# dclass-amp.net
KiCad netlist of a schematic drawn in Altium Designer
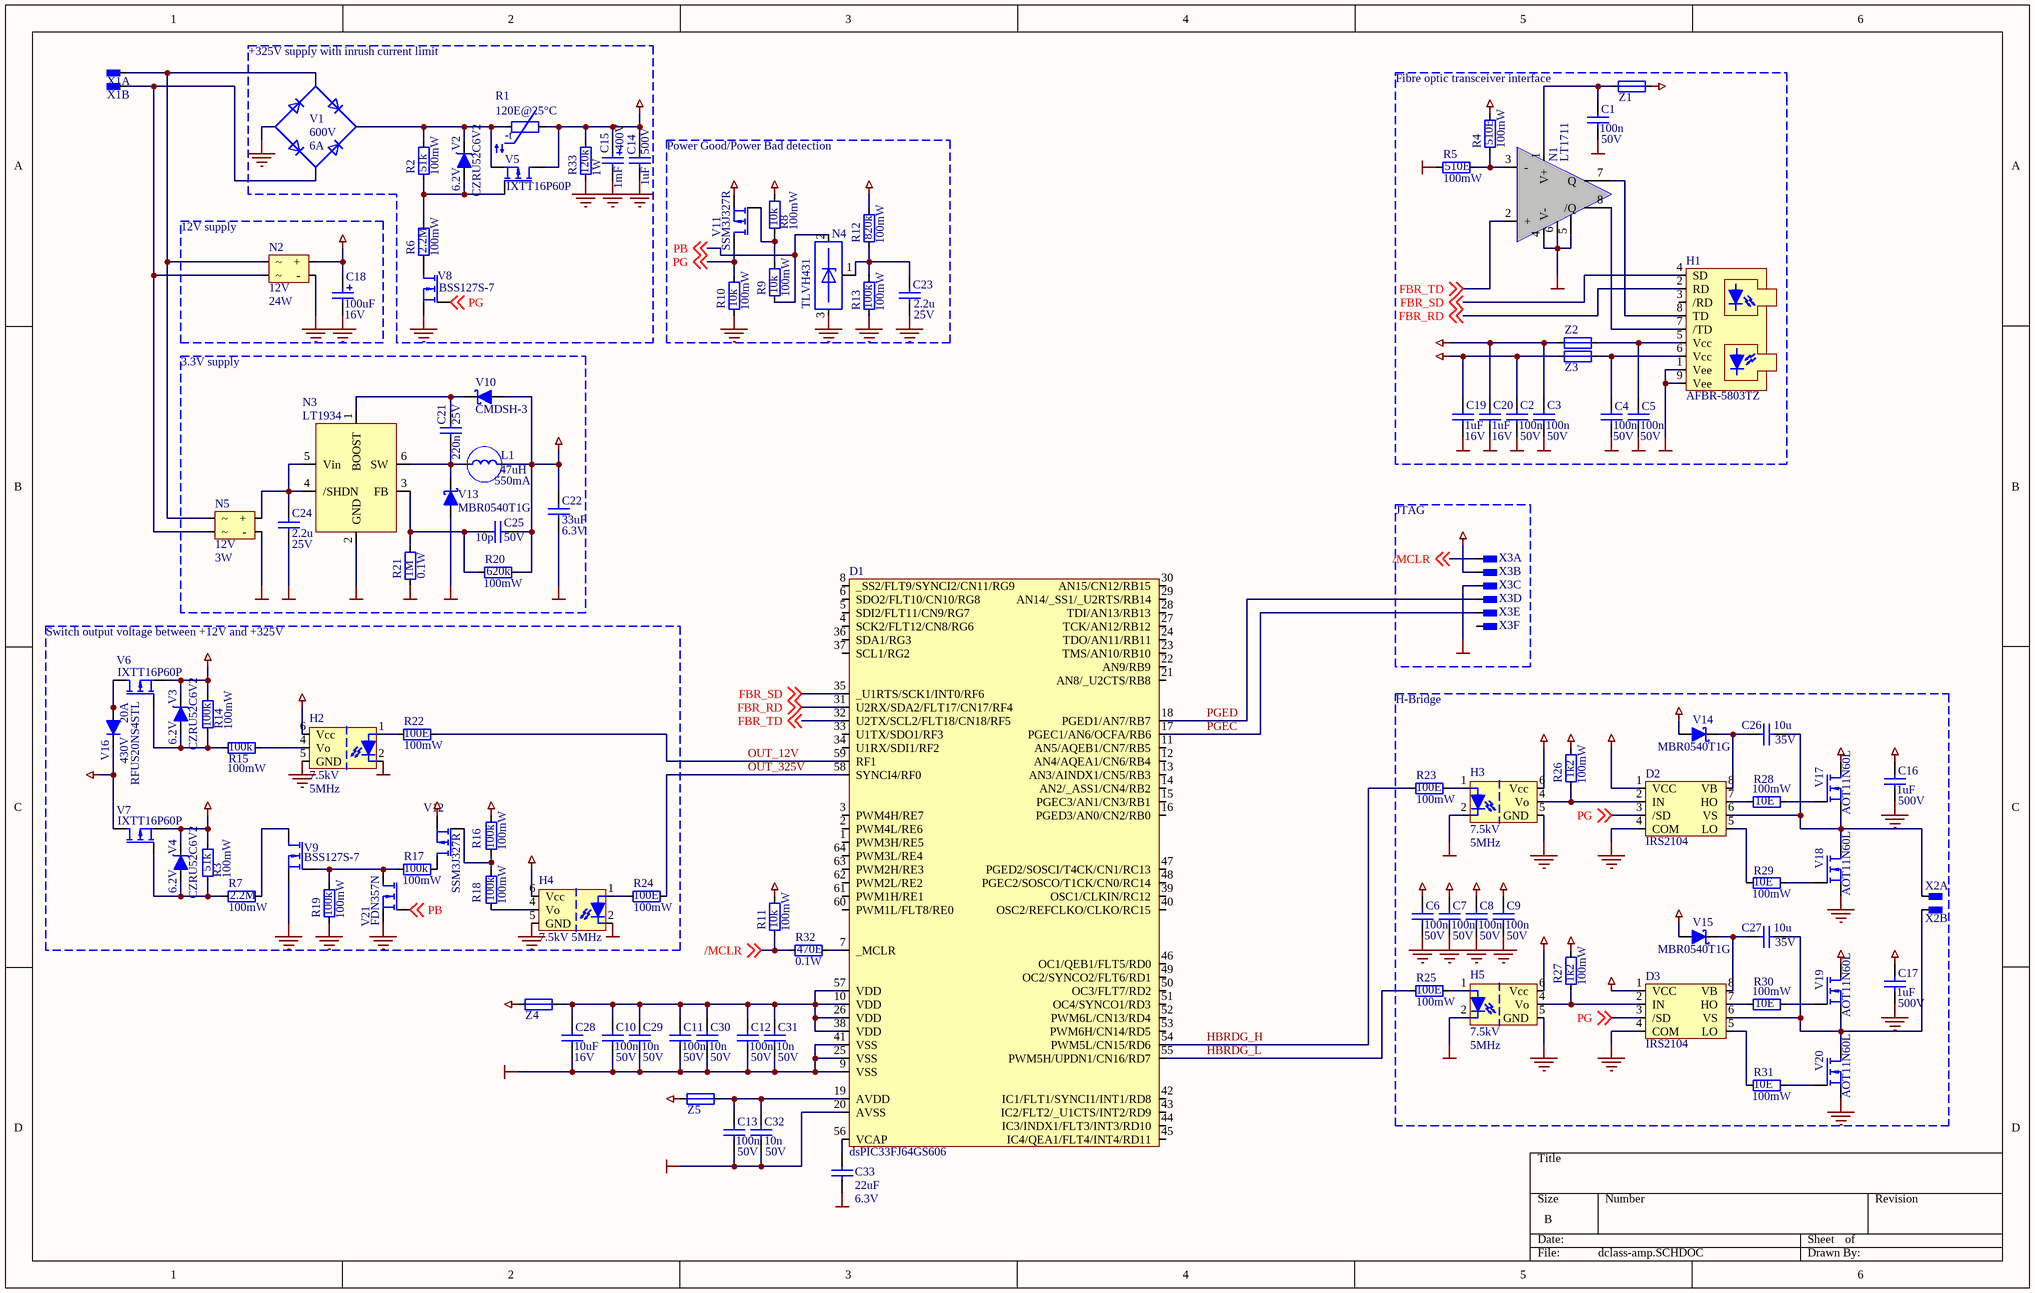
[diagram p0: dclass-amp.SCHDOC]

(export (version "E")
  (design (tool "Eeschema 10.0.6"))
  (components
    (comp (ref "C1")
      (value "C_SMD_CER_100N_50V_10%_X7R_0603")
      (footprint "SMD_0603")
      (description "SMD Capacitor")
      (fields (field (name "ALTIUM_VALUE") "100n") (field (name "VALUE2") "50V"))
      (libsource (lib "AM") (part "C_SMD_CER_100N_50V_10%_X7R_0603"))
    )
    (comp (ref "C2")
      (value "C_SMD_CER_100N_50V_10%_X7R_0603")
      (footprint "SMD_0603")
      (description "SMD Capacitor")
      (fields (field (name "ALTIUM_VALUE") "100n") (field (name "VALUE2") "50V"))
      (libsource (lib "AM") (part "C_SMD_CER_100N_50V_10%_X7R_0603"))
    )
    (comp (ref "C3")
      (value "C_SMD_CER_100N_50V_10%_X7R_0603")
      (footprint "SMD_0603")
      (description "SMD Capacitor")
      (fields (field (name "ALTIUM_VALUE") "100n") (field (name "VALUE2") "50V"))
      (libsource (lib "AM") (part "C_SMD_CER_100N_50V_10%_X7R_0603"))
    )
    (comp (ref "C4")
      (value "C_SMD_CER_100N_50V_10%_X7R_0603")
      (footprint "SMD_0603")
      (description "SMD Capacitor")
      (fields (field (name "ALTIUM_VALUE") "100n") (field (name "VALUE2") "50V"))
      (libsource (lib "AM") (part "C_SMD_CER_100N_50V_10%_X7R_0603"))
    )
    (comp (ref "C5")
      (value "C_SMD_CER_100N_50V_10%_X7R_0603")
      (footprint "SMD_0603")
      (description "SMD Capacitor")
      (fields (field (name "ALTIUM_VALUE") "100n") (field (name "VALUE2") "50V"))
      (libsource (lib "AM") (part "C_SMD_CER_100N_50V_10%_X7R_0603"))
    )
    (comp (ref "C6")
      (value "C_SMD_CER_100N_50V_10%_X7R_0603")
      (footprint "SMD_0603")
      (description "SMD Capacitor")
      (fields (field (name "ALTIUM_VALUE") "100n") (field (name "VALUE2") "50V"))
      (libsource (lib "AM") (part "C_SMD_CER_100N_50V_10%_X7R_0603"))
    )
    (comp (ref "C7")
      (value "C_SMD_CER_100N_50V_10%_X7R_0603")
      (footprint "SMD_0603")
      (description "SMD Capacitor")
      (fields (field (name "ALTIUM_VALUE") "100n") (field (name "VALUE2") "50V"))
      (libsource (lib "AM") (part "C_SMD_CER_100N_50V_10%_X7R_0603"))
    )
    (comp (ref "C8")
      (value "C_SMD_CER_100N_50V_10%_X7R_0603")
      (footprint "SMD_0603")
      (description "SMD Capacitor")
      (fields (field (name "ALTIUM_VALUE") "100n") (field (name "VALUE2") "50V"))
      (libsource (lib "AM") (part "C_SMD_CER_100N_50V_10%_X7R_0603"))
    )
    (comp (ref "C9")
      (value "C_SMD_CER_100N_50V_10%_X7R_0603")
      (footprint "SMD_0603")
      (description "SMD Capacitor")
      (fields (field (name "ALTIUM_VALUE") "100n") (field (name "VALUE2") "50V"))
      (libsource (lib "AM") (part "C_SMD_CER_100N_50V_10%_X7R_0603"))
    )
    (comp (ref "C10")
      (value "C_SMD_CER_100N_50V_10%_X7R_0603")
      (footprint "SMD_0603")
      (description "SMD Capacitor")
      (fields (field (name "ALTIUM_VALUE") "100n") (field (name "VALUE2") "50V"))
      (libsource (lib "AM") (part "C_SMD_CER_100N_50V_10%_X7R_0603"))
    )
    (comp (ref "C11")
      (value "C_SMD_CER_100N_50V_10%_X7R_0603")
      (footprint "SMD_0603")
      (description "SMD Capacitor")
      (fields (field (name "ALTIUM_VALUE") "100n") (field (name "VALUE2") "50V"))
      (libsource (lib "AM") (part "C_SMD_CER_100N_50V_10%_X7R_0603"))
    )
    (comp (ref "C12")
      (value "C_SMD_CER_100N_50V_10%_X7R_0603")
      (footprint "SMD_0603")
      (description "SMD Capacitor")
      (fields (field (name "ALTIUM_VALUE") "100n") (field (name "VALUE2") "50V"))
      (libsource (lib "AM") (part "C_SMD_CER_100N_50V_10%_X7R_0603"))
    )
    (comp (ref "C13")
      (value "C_SMD_CER_100N_50V_10%_X7R_0603")
      (footprint "SMD_0603")
      (description "SMD Capacitor")
      (fields (field (name "ALTIUM_VALUE") "100n") (field (name "VALUE2") "50V"))
      (libsource (lib "AM") (part "C_SMD_CER_100N_50V_10%_X7R_0603"))
    )
    (comp (ref "C14")
      (value "C_THT_ALU_1000U_400V_20%_T2GP102FA")
      (footprint "THT_CAP_T2GP102FA")
      (description "THT Aluminum capacitor")
      (fields (field (name "ALTIUM_VALUE") "1mF") (field (name "VALUE2") "400V"))
      (libsource (lib "AM") (part "C_THT_ALU_1000U_400V_20%_T2GP102FA"))
    )
    (comp (ref "C15")
      (value "C_SMD_CER_1U_500V_20%_X7R_2220")
      (footprint "SMD_2220")
      (fields (field (name "ALTIUM_VALUE") "1uF") (field (name "VALUE2") "500V"))
      (libsource (lib "AM") (part "C_SMD_CER_1U_500V_20%_X7R_2220"))
    )
    (comp (ref "C16")
      (value "C_SMD_CER_1U_500V_20%_X7R_2220")
      (footprint "SMD_2220")
      (fields (field (name "ALTIUM_VALUE") "1uF") (field (name "VALUE2") "500V"))
      (libsource (lib "AM") (part "C_SMD_CER_1U_500V_20%_X7R_2220"))
    )
    (comp (ref "C17")
      (value "C_SMD_CER_1U_500V_20%_X7R_2220")
      (footprint "SMD_2220")
      (fields (field (name "ALTIUM_VALUE") "1uF") (field (name "VALUE2") "500V"))
      (libsource (lib "AM") (part "C_SMD_CER_1U_500V_20%_X7R_2220"))
    )
    (comp (ref "C18")
      (value "C_SMD_TAN_100U_16V_20%_7343")
      (footprint "SMD_7343P")
      (description "SMD Tantal Capacitor")
      (fields (field (name "ALTIUM_VALUE") "100uF") (field (name "VALUE2") "16V"))
      (libsource (lib "AM") (part "C_SMD_TAN_100U_16V_20%_7343"))
    )
    (comp (ref "C19")
      (value "C_SMD_CER_1U_16V_10%_X5R_0603")
      (footprint "SMD_0603")
      (description "SMD Capacitor")
      (fields (field (name "ALTIUM_VALUE") "1uF") (field (name "VALUE2") "16V"))
      (libsource (lib "AM") (part "C_SMD_CER_1U_16V_10%_X5R_0603"))
    )
    (comp (ref "C20")
      (value "C_SMD_CER_1U_16V_10%_X5R_0603")
      (footprint "SMD_0603")
      (description "SMD Capacitor")
      (fields (field (name "ALTIUM_VALUE") "1uF") (field (name "VALUE2") "16V"))
      (libsource (lib "AM") (part "C_SMD_CER_1U_16V_10%_X5R_0603"))
    )
    (comp (ref "C21")
      (value "C_SMD_CER_220N_25V_10%_X5R_0603")
      (footprint "SMD_0603")
      (description "SMD Capacitor")
      (fields (field (name "ALTIUM_VALUE") "220n") (field (name "VALUE2") "25V"))
      (libsource (lib "AM") (part "C_SMD_CER_220N_25V_10%_X5R_0603"))
    )
    (comp (ref "C22")
      (value "C_SMD_CER_33U_6V3_20%_X5R_1206")
      (footprint "SMD_1206")
      (fields (field (name "ALTIUM_VALUE") "33uF") (field (name "VALUE2") "6.3V"))
      (libsource (lib "AM") (part "C_SMD_CER_33U_6V3_20%_X5R_1206"))
    )
    (comp (ref "C23")
      (value "C_SMD_CER_2U2_25V_10%_X5R_0603")
      (footprint "SMD_0603")
      (description "SMD Capacitor")
      (fields (field (name "ALTIUM_VALUE") "2.2u") (field (name "VALUE2") "25V"))
      (libsource (lib "AM") (part "C_SMD_CER_2U2_25V_10%_X5R_0603"))
    )
    (comp (ref "C24")
      (value "C_SMD_CER_2U2_25V_10%_X5R_0603")
      (footprint "SMD_0603")
      (description "SMD Capacitor")
      (fields (field (name "ALTIUM_VALUE") "2.2u") (field (name "VALUE2") "25V"))
      (libsource (lib "AM") (part "C_SMD_CER_2U2_25V_10%_X5R_0603"))
    )
    (comp (ref "C25")
      (value "C_SMD_CER_10P_50V_5%_NP0_0603")
      (footprint "SMD_0603")
      (description "SMD Capacitor")
      (fields (field (name "ALTIUM_VALUE") "10p") (field (name "VALUE2") "50V"))
      (libsource (lib "AM") (part "C_SMD_CER_10P_50V_5%_NP0_0603"))
    )
    (comp (ref "C26")
      (value "C_SMD_CER_10U_35V_10%_X5R_1206")
      (footprint "SMD_1206")
      (description "SMD Capacitor, 10uF, 35V, 1206")
      (fields (field (name "ALTIUM_VALUE") "10u") (field (name "VALUE2") "35V"))
      (libsource (lib "AM") (part "C_SMD_CER_10U_35V_10%_X5R_1206"))
    )
    (comp (ref "C27")
      (value "C_SMD_CER_10U_35V_10%_X5R_1206")
      (footprint "SMD_1206")
      (description "SMD Capacitor, 10uF, 35V, 1206")
      (fields (field (name "ALTIUM_VALUE") "10u") (field (name "VALUE2") "35V"))
      (libsource (lib "AM") (part "C_SMD_CER_10U_35V_10%_X5R_1206"))
    )
    (comp (ref "C28")
      (value "C_SMD_CER_10U_16V_10%_X5R_0805")
      (footprint "SMD_0805")
      (description "SMD Capacitor")
      (fields (field (name "ALTIUM_VALUE") "10uF") (field (name "VALUE2") "16V"))
      (libsource (lib "AM") (part "C_SMD_CER_10U_16V_10%_X5R_0805"))
    )
    (comp (ref "C29")
      (value "C_SMD_CER_10N_50V_10%_X7R_0603")
      (footprint "SMD_0603")
      (description "SMD Capacitor")
      (fields (field (name "ALTIUM_VALUE") "10n") (field (name "VALUE2") "50V"))
      (libsource (lib "AM") (part "C_SMD_CER_10N_50V_10%_X7R_0603"))
    )
    (comp (ref "C30")
      (value "C_SMD_CER_10N_50V_10%_X7R_0603")
      (footprint "SMD_0603")
      (description "SMD Capacitor")
      (fields (field (name "ALTIUM_VALUE") "10n") (field (name "VALUE2") "50V"))
      (libsource (lib "AM") (part "C_SMD_CER_10N_50V_10%_X7R_0603"))
    )
    (comp (ref "C31")
      (value "C_SMD_CER_10N_50V_10%_X7R_0603")
      (footprint "SMD_0603")
      (description "SMD Capacitor")
      (fields (field (name "ALTIUM_VALUE") "10n") (field (name "VALUE2") "50V"))
      (libsource (lib "AM") (part "C_SMD_CER_10N_50V_10%_X7R_0603"))
    )
    (comp (ref "C32")
      (value "C_SMD_CER_10N_50V_10%_X7R_0603")
      (footprint "SMD_0603")
      (description "SMD Capacitor")
      (fields (field (name "ALTIUM_VALUE") "10n") (field (name "VALUE2") "50V"))
      (libsource (lib "AM") (part "C_SMD_CER_10N_50V_10%_X7R_0603"))
    )
    (comp (ref "C33")
      (value "C_SMD_CER_22U_6V3_20%_X5R_1206")
      (footprint "SMD_1206")
      (description "SMD Capacitor")
      (fields (field (name "ALTIUM_VALUE") "22uF") (field (name "VALUE2") "6.3V"))
      (libsource (lib "AM") (part "C_SMD_CER_22U_6V3_20%_X5R_1206"))
    )
    (comp (ref "D1")
      (value "D_DSPIC33FJ64GS606_TQFP-64")
      (footprint "SMD_TQFP-64")
      (fields (field (name "TYPE") "dsPIC33FJ64GS606"))
      (libsource (lib "AM") (part "D_DSPIC33FJ64GS606_TQFP-64"))
    )
    (comp (ref "D2")
      (value "D_IRS2104SPBF_SOP-8")
      (footprint "SMD_SOP_8")
      (description "Half-Bridge Driver, 600V")
      (fields (field (name "TYPE") "IRS2104"))
      (libsource (lib "AM") (part "D_IRS2104SPBF_SOP-8"))
    )
    (comp (ref "D3")
      (value "D_IRS2104SPBF_SOP-8")
      (footprint "SMD_SOP_8")
      (description "Half-Bridge Driver, 600V")
      (fields (field (name "TYPE") "IRS2104"))
      (libsource (lib "AM") (part "D_IRS2104SPBF_SOP-8"))
    )
    (comp (ref "H1")
      (value "H_OPTO_TRANSCEIVER_ST_3V3_100MBPS_1300NM")
      (footprint "THT_AFBR-5803TZ")
      (fields (field (name "TYPE") "AFBR-5803TZ"))
      (libsource (lib "AM") (part "H_OPTO_TRANSCEIVER_ST_3V3_100MBPS_1300NM"))
    )
    (comp (ref "H2")
      (value "H_OPTOISOLATOR_7500V_5MHZ_SMD-6")
      (footprint "SMD-6")
      (fields (field (name "ALTIUM_VALUE") "7.5kV") (field (name "VALUE2") "5MHz"))
      (libsource (lib "") (part "H_OPTOISOLATOR_7500V_5MHZ_SMD-6_1"))
    )
    (comp (ref "H3")
      (value "H_OPTOISOLATOR_7500V_5MHZ_SMD-6")
      (footprint "SMD-6")
      (fields (field (name "ALTIUM_VALUE") "7.5kV") (field (name "VALUE2") "5MHz"))
      (libsource (lib "AM") (part "H_OPTOISOLATOR_7500V_5MHZ_SMD-6"))
    )
    (comp (ref "H4")
      (value "H_OPTOISOLATOR_7500V_5MHZ_SMD-6")
      (footprint "SMD-6")
      (fields (field (name "ALTIUM_VALUE") "7.5kV") (field (name "VALUE2") "5MHz"))
      (libsource (lib "") (part "H_OPTOISOLATOR_7500V_5MHZ_SMD-6_1"))
    )
    (comp (ref "H5")
      (value "H_OPTOISOLATOR_7500V_5MHZ_SMD-6")
      (footprint "SMD-6")
      (fields (field (name "ALTIUM_VALUE") "7.5kV") (field (name "VALUE2") "5MHz"))
      (libsource (lib "AM") (part "H_OPTOISOLATOR_7500V_5MHZ_SMD-6"))
    )
    (comp (ref "L1")
      (value "L_SMD_47U_0A55_20%")
      (footprint "SMD_INDUCT-74404041470")
      (description "SMD Inductor")
      (fields (field (name "ALTIUM_VALUE") "47uH") (field (name "VALUE2") "550mA"))
      (libsource (lib "AM") (part "L_SMD_47U_0A55_20%"))
    )
    (comp (ref "N1")
      (value "N_LT1711_SOP-8")
      (footprint "SMD_SOP_8")
      (description "Rail-to-rail Voltage Comparator")
      (fields (field (name "TYPE") "LT1711"))
      (libsource (lib "AM") (part "N_LT1711_SOP-8"))
    )
    (comp (ref "N2")
      (value "N_SMPS_265AC-to-12V_24W")
      (footprint "THT_VCP24US12-E")
      (fields (field (name "ALTIUM_VALUE") "12V") (field (name "VALUE2") "24W"))
      (libsource (lib "AM") (part "N_SMPS_265AC-to-12V_24W"))
    )
    (comp (ref "N3")
      (value "LT1934")
      (footprint "SMD_SOT_23_6")
      (description "Micropower Step-Down Switching Regulators")
      (fields (field (name "TYPE") "LT1934"))
      (libsource (lib "AM") (part "N_LT1934_SOT-23-6"))
    )
    (comp (ref "N4")
      (value "N_TLVH431_SOT23-3")
      (footprint "SMD_SOT_23_3")
      (description "LOW-VOLTAGE ADJUSTABLE PRECISION SHUNT REGULATORS")
      (fields (field (name "TYPE") "TLVH431"))
      (libsource (lib "AM") (part "N_TLVH431_SOT23-3"))
    )
    (comp (ref "N5")
      (value "N_SMPS_12V_3W")
      (footprint "THT_SPAC265BC12P0.30")
      (fields (field (name "ALTIUM_VALUE") "12V") (field (name "VALUE2") "3W"))
      (libsource (lib "AM") (part "N_SMPS_12V_3W"))
    )
    (comp (ref "R1")
      (value "R_THT_NTC_120E_20%")
      (footprint "THT_R_A_L17.5_D6_P10")
      (description "CURRENT LIMITER INRUSH 120OHM 20%")
      (fields (field (name "ALTIUM_VALUE") "120E@25°C"))
      (libsource (lib "AM") (part "R_THT_NTC_120E_20%"))
    )
    (comp (ref "R2")
      (value "R_SMD_THINFILM_51K_0W1_1%_50PPM_0603")
      (footprint "SMD_0603")
      (description "SMD Resistor")
      (fields (field (name "ALTIUM_VALUE") "51k") (field (name "VALUE2") "100mW"))
      (libsource (lib "AM") (part "R_SMD_THINFILM_51K_0W1_1%_50PPM_0603"))
    )
    (comp (ref "R3")
      (value "R_SMD_THINFILM_51K_0W1_1%_50PPM_0603")
      (footprint "SMD_0603")
      (description "SMD Resistor")
      (fields (field (name "ALTIUM_VALUE") "51k") (field (name "VALUE2") "100mW"))
      (libsource (lib "AM") (part "R_SMD_THINFILM_51K_0W1_1%_50PPM_0603"))
    )
    (comp (ref "R4")
      (value "R_SMD_THINFILM_510E_0W1_0.1%_25PPM_0603")
      (footprint "SMD_0603")
      (description "SMD Resistor")
      (fields (field (name "ALTIUM_VALUE") "510E") (field (name "VALUE2") "100mW"))
      (libsource (lib "AM") (part "R_SMD_THINFILM_510E_0W1_0.1%_25PPM_0603"))
    )
    (comp (ref "R5")
      (value "R_SMD_THINFILM_510E_0W1_0.1%_25PPM_0603")
      (footprint "SMD_0603")
      (description "SMD Resistor")
      (fields (field (name "ALTIUM_VALUE") "510E") (field (name "VALUE2") "100mW"))
      (libsource (lib "AM") (part "R_SMD_THINFILM_510E_0W1_0.1%_25PPM_0603"))
    )
    (comp (ref "R6")
      (value "R_SMD_THINFILM_2M2_0W1_1%_50PPM_0603")
      (footprint "SMD_0603")
      (description "SMD Resistor")
      (fields (field (name "ALTIUM_VALUE") "2.2M") (field (name "VALUE2") "100mW"))
      (libsource (lib "AM") (part "R_SMD_THINFILM_2M2_0W1_1%_50PPM_0603"))
    )
    (comp (ref "R7")
      (value "R_SMD_THINFILM_2M2_0W1_1%_50PPM_0603")
      (footprint "SMD_0603")
      (description "SMD Resistor")
      (fields (field (name "ALTIUM_VALUE") "2.2M") (field (name "VALUE2") "100mW"))
      (libsource (lib "AM") (part "R_SMD_THINFILM_2M2_0W1_1%_50PPM_0603"))
    )
    (comp (ref "R8")
      (value "R_SMD_THINFILM_10K_0W1_1%_50PPM_0603")
      (footprint "SMD_0603")
      (description "SMD Resistor")
      (fields (field (name "ALTIUM_VALUE") "10k") (field (name "VALUE2") "100mW"))
      (libsource (lib "AM") (part "R_SMD_THINFILM_10K_0W1_1%_50PPM_0603"))
    )
    (comp (ref "R9")
      (value "R_SMD_THINFILM_10K_0W1_1%_50PPM_0603")
      (footprint "SMD_0603")
      (description "SMD Resistor")
      (fields (field (name "ALTIUM_VALUE") "10k") (field (name "VALUE2") "100mW"))
      (libsource (lib "AM") (part "R_SMD_THINFILM_10K_0W1_1%_50PPM_0603"))
    )
    (comp (ref "R10")
      (value "R_SMD_THINFILM_10K_0W1_1%_50PPM_0603")
      (footprint "SMD_0603")
      (description "SMD Resistor")
      (fields (field (name "ALTIUM_VALUE") "10k") (field (name "VALUE2") "100mW"))
      (libsource (lib "AM") (part "R_SMD_THINFILM_10K_0W1_1%_50PPM_0603"))
    )
    (comp (ref "R11")
      (value "R_SMD_THINFILM_10K_0W1_1%_50PPM_0603")
      (footprint "SMD_0603")
      (description "SMD Resistor")
      (fields (field (name "ALTIUM_VALUE") "10k") (field (name "VALUE2") "100mW"))
      (libsource (lib "AM") (part "R_SMD_THINFILM_10K_0W1_1%_50PPM_0603"))
    )
    (comp (ref "R12")
      (value "R_SMD_THINFILM_820K_0W1_1%_100PPM_0603")
      (footprint "SMD_0603")
      (description "SMD Resistor")
      (fields (field (name "ALTIUM_VALUE") "820k") (field (name "VALUE2") "100mW"))
      (libsource (lib "AM") (part "R_SMD_THINFILM_820K_0W1_1%_100PPM_0603"))
    )
    (comp (ref "R13")
      (value "R_SMD_THINFILM_100K_0W1_1%_50PPM_0603")
      (footprint "SMD_0603")
      (description "SMD Resistor")
      (fields (field (name "ALTIUM_VALUE") "100k") (field (name "VALUE2") "100mW"))
      (libsource (lib "AM") (part "R_SMD_THINFILM_100K_0W1_1%_50PPM_0603"))
    )
    (comp (ref "R14")
      (value "R_SMD_THINFILM_100K_0W1_1%_50PPM_0603")
      (footprint "SMD_0603")
      (description "SMD Resistor")
      (fields (field (name "ALTIUM_VALUE") "100k") (field (name "VALUE2") "100mW"))
      (libsource (lib "AM") (part "R_SMD_THINFILM_100K_0W1_1%_50PPM_0603"))
    )
    (comp (ref "R15")
      (value "R_SMD_THINFILM_100K_0W1_1%_50PPM_0603")
      (footprint "SMD_0603")
      (description "SMD Resistor")
      (fields (field (name "ALTIUM_VALUE") "100k") (field (name "VALUE2") "100mW"))
      (libsource (lib "AM") (part "R_SMD_THINFILM_100K_0W1_1%_50PPM_0603"))
    )
    (comp (ref "R16")
      (value "R_SMD_THINFILM_100K_0W1_1%_50PPM_0603")
      (footprint "SMD_0603")
      (description "SMD Resistor")
      (fields (field (name "ALTIUM_VALUE") "100k") (field (name "VALUE2") "100mW"))
      (libsource (lib "AM") (part "R_SMD_THINFILM_100K_0W1_1%_50PPM_0603"))
    )
    (comp (ref "R17")
      (value "R_SMD_THINFILM_100K_0W1_1%_50PPM_0603")
      (footprint "SMD_0603")
      (description "SMD Resistor")
      (fields (field (name "ALTIUM_VALUE") "100k") (field (name "VALUE2") "100mW"))
      (libsource (lib "AM") (part "R_SMD_THINFILM_100K_0W1_1%_50PPM_0603"))
    )
    (comp (ref "R18")
      (value "R_SMD_THINFILM_100K_0W1_1%_50PPM_0603")
      (footprint "SMD_0603")
      (description "SMD Resistor")
      (fields (field (name "ALTIUM_VALUE") "100k") (field (name "VALUE2") "100mW"))
      (libsource (lib "AM") (part "R_SMD_THINFILM_100K_0W1_1%_50PPM_0603"))
    )
    (comp (ref "R19")
      (value "R_SMD_THINFILM_100K_0W1_1%_50PPM_0603")
      (footprint "SMD_0603")
      (description "SMD Resistor")
      (fields (field (name "ALTIUM_VALUE") "100k") (field (name "VALUE2") "100mW"))
      (libsource (lib "AM") (part "R_SMD_THINFILM_100K_0W1_1%_50PPM_0603"))
    )
    (comp (ref "R20")
      (value "R_SMD_THINFILM_620K_0W1_1%_50PPM_0603")
      (footprint "SMD_0603")
      (description "SMD Resistor")
      (fields (field (name "ALTIUM_VALUE") "620k") (field (name "VALUE2") "100mW"))
      (libsource (lib "AM") (part "R_SMD_THINFILM_620K_0W1_1%_50PPM_0603"))
    )
    (comp (ref "R21")
      (value "R_SMD_THINFILM_1M_0W1_1%_50PPM_0603")
      (footprint "SMD_0603")
      (description "SMD Resistor")
      (fields (field (name "ALTIUM_VALUE") "1M") (field (name "VALUE2") "0.1W"))
      (libsource (lib "AM") (part "R_SMD_THINFILM_1M_0W1_1%_50PPM_0603"))
    )
    (comp (ref "R22")
      (value "R_SMD_THINFILM_100E_0W1_1%_50PPM_0603")
      (footprint "SMD_0603")
      (description "SMD Resistor")
      (fields (field (name "ALTIUM_VALUE") "100E") (field (name "VALUE2") "100mW"))
      (libsource (lib "AM") (part "R_SMD_THINFILM_100E_0W1_1%_50PPM_0603"))
    )
    (comp (ref "R23")
      (value "R_SMD_THINFILM_100E_0W1_1%_50PPM_0603")
      (footprint "SMD_0603")
      (description "SMD Resistor")
      (fields (field (name "ALTIUM_VALUE") "100E") (field (name "VALUE2") "100mW"))
      (libsource (lib "AM") (part "R_SMD_THINFILM_100E_0W1_1%_50PPM_0603"))
    )
    (comp (ref "R24")
      (value "R_SMD_THINFILM_100E_0W1_1%_50PPM_0603")
      (footprint "SMD_0603")
      (description "SMD Resistor")
      (fields (field (name "ALTIUM_VALUE") "100E") (field (name "VALUE2") "100mW"))
      (libsource (lib "AM") (part "R_SMD_THINFILM_100E_0W1_1%_50PPM_0603"))
    )
    (comp (ref "R25")
      (value "R_SMD_THINFILM_100E_0W1_1%_50PPM_0603")
      (footprint "SMD_0603")
      (description "SMD Resistor")
      (fields (field (name "ALTIUM_VALUE") "100E") (field (name "VALUE2") "100mW"))
      (libsource (lib "AM") (part "R_SMD_THINFILM_100E_0W1_1%_50PPM_0603"))
    )
    (comp (ref "R26")
      (value "R_SMD_THINFILM_1K_0W1_1%_50PPM_0603")
      (footprint "SMD_0603")
      (description "SMD Resistor")
      (fields (field (name "ALTIUM_VALUE") "1k2") (field (name "VALUE2") "100mW"))
      (libsource (lib "AM") (part "R_SMD_THINFILM_1K2_0W1_1%_50PPM_0603"))
    )
    (comp (ref "R27")
      (value "R_SMD_THINFILM_1K_0W1_1%_50PPM_0603")
      (footprint "SMD_0603")
      (description "SMD Resistor")
      (fields (field (name "ALTIUM_VALUE") "1k2") (field (name "VALUE2") "100mW"))
      (libsource (lib "AM") (part "R_SMD_THINFILM_1K2_0W1_1%_50PPM_0603"))
    )
    (comp (ref "R28")
      (value "R_SMD_THINFILM_10E_0W1_1%_50PPM_0603")
      (footprint "SMD_0603")
      (description "SMD Resistor")
      (fields (field (name "ALTIUM_VALUE") "10E") (field (name "VALUE2") "100mW"))
      (libsource (lib "AM") (part "R_SMD_THINFILM_10E_0W1_1%_50PPM_0603"))
    )
    (comp (ref "R29")
      (value "R_SMD_THINFILM_10E_0W1_1%_50PPM_0603")
      (footprint "SMD_0603")
      (description "SMD Resistor")
      (fields (field (name "ALTIUM_VALUE") "10E") (field (name "VALUE2") "100mW"))
      (libsource (lib "AM") (part "R_SMD_THINFILM_10E_0W1_1%_50PPM_0603"))
    )
    (comp (ref "R30")
      (value "R_SMD_THINFILM_10E_0W1_1%_50PPM_0603")
      (footprint "SMD_0603")
      (description "SMD Resistor")
      (fields (field (name "ALTIUM_VALUE") "10E") (field (name "VALUE2") "100mW"))
      (libsource (lib "AM") (part "R_SMD_THINFILM_10E_0W1_1%_50PPM_0603"))
    )
    (comp (ref "R31")
      (value "R_SMD_THINFILM_10E_0W1_1%_50PPM_0603")
      (footprint "SMD_0603")
      (description "SMD Resistor")
      (fields (field (name "ALTIUM_VALUE") "10E") (field (name "VALUE2") "100mW"))
      (libsource (lib "AM") (part "R_SMD_THINFILM_10E_0W1_1%_50PPM_0603"))
    )
    (comp (ref "R32")
      (value "R_SMD_THINFILM_470E_0W1_1%_50PPM_0603")
      (footprint "SMD_0603")
      (description "SMD Resistor")
      (fields (field (name "ALTIUM_VALUE") "470E") (field (name "VALUE2") "0.1W"))
      (libsource (lib "AM") (part "R_SMD_THINFILM_470E_0W1_1%_50PPM_0603"))
    )
    (comp (ref "R33")
      (value "R_THT_METALOXIDEFILM_120K_1W_5%_200PPM")
      (footprint "THT_R_A_L14.0_W5.0_P10.0")
      (fields (field (name "ALTIUM_VALUE") "120k") (field (name "VALUE2") "1W"))
      (libsource (lib "AM") (part "R_THT_METALOXIDEFILM_120K_1W_5%_200PPM"))
    )
    (comp (ref "V1")
      (value "V_THT_BRIDGE_RECTIFIER_KBU6J_600V_6A_KBU")
      (footprint "THT_KBU6J")
      (description "Bridge Recitifer")
      (fields (field (name "ALTIUM_VALUE") "600V") (field (name "VALUE2") "6A"))
      (libsource (lib "AM") (part "V_THT_BRIDGE_RECTIFIER_KBU6J_600V_6A_KBU"))
    )
    (comp (ref "V2")
      (value "V_SMD_Z-DIODE_CZRU52C6V2_6V2_0W15_5%_0603")
      (footprint "SMD_0603P")
      (description "Zener Diode, 6.2V")
      (fields (field (name "TYPE") "CZRU52C6V2") (field (name "ALTIUM_VALUE") "6.2V"))
      (libsource (lib "AM") (part "V_SMD_Z-DIODE_CZRU52C6V2_6V2_0W15_5%_0603"))
    )
    (comp (ref "V3")
      (value "V_SMD_Z-DIODE_CZRU52C6V2_6V2_0W15_5%_0603")
      (footprint "SMD_0603P")
      (description "Zener Diode, 6.2V")
      (fields (field (name "TYPE") "CZRU52C6V2") (field (name "ALTIUM_VALUE") "6.2V"))
      (libsource (lib "AM") (part "V_SMD_Z-DIODE_CZRU52C6V2_6V2_0W15_5%_0603"))
    )
    (comp (ref "V4")
      (value "V_SMD_Z-DIODE_CZRU52C6V2_6V2_0W15_5%_0603")
      (footprint "SMD_0603P")
      (description "Zener Diode, 6.2V")
      (fields (field (name "TYPE") "CZRU52C6V2") (field (name "ALTIUM_VALUE") "6.2V"))
      (libsource (lib "AM") (part "V_SMD_Z-DIODE_CZRU52C6V2_6V2_0W15_5%_0603"))
    )
    (comp (ref "V5")
      (value "V_SMD_FET_IXTT16P60P_PMOS_600V_16A_92NC_460W_TO-268-3")
      (footprint "SMD_TO-268-3")
      (description "P-Channel Power MOSFET")
      (fields (field (name "TYPE") "IXTT16P60P"))
      (libsource (lib "AM") (part "V_SMD_FET_PMOS_600V_16A_92NC_460W_TO-268-3"))
    )
    (comp (ref "V6")
      (value "V_SMD_FET_IXTT16P60P_PMOS_600V_16A_92NC_460W_TO-268-3")
      (footprint "SMD_TO-268-3")
      (description "P-Channel Power MOSFET")
      (fields (field (name "TYPE") "IXTT16P60P"))
      (libsource (lib "AM") (part "V_SMD_FET_PMOS_600V_16A_92NC_460W_TO-268-3"))
    )
    (comp (ref "V7")
      (value "V_SMD_FET_IXTT16P60P_PMOS_600V_16A_92NC_460W_TO-268-3")
      (footprint "SMD_TO-268-3")
      (description "P-Channel Power MOSFET")
      (fields (field (name "TYPE") "IXTT16P60P"))
      (libsource (lib "AM") (part "V_SMD_FET_PMOS_600V_16A_92NC_460W_TO-268-3"))
    )
    (comp (ref "V8")
      (value "V_SMD_FET_NMOS_BSS127S-7_600V_0A05_1NC08_0W61_SOT-23-3")
      (footprint "SMD_SOT_23_3")
      (description "N-Channel Logic Level Enhancement Mode Field Effect Transistor")
      (fields (field (name "TYPE") "BSS127S-7"))
      (libsource (lib "AM") (part "V_SMD_FET_NMOS_BSS127S-7_600V_0A05_1NC08_0W61_SOT-23-3"))
    )
    (comp (ref "V9")
      (value "V_SMD_FET_NMOS_BSS127S-7_600V_0A05_1NC08_0W61_SOT-23-3")
      (footprint "SMD_SOT_23_3")
      (description "N-Channel Logic Level Enhancement Mode Field Effect Transistor")
      (fields (field (name "TYPE") "BSS127S-7"))
      (libsource (lib "AM") (part "V_SMD_FET_NMOS_BSS127S-7_600V_0A05_1NC08_0W61_SOT-23-3"))
    )
    (comp (ref "V10")
      (value "V_SMD_SCHOTTKY_MBR0540T1G_40V_0A5_SOD-123")
      (footprint "SMD_SOD_323")
      (description "Schottky diode, 30V, 100mA, SOD-323")
      (fields (field (name "TYPE") "CMDSH-3"))
      (libsource (lib "AM") (part "V_SMD_SCHOTTKY_CMDSH-3_30V_0A1_SOD-323_1"))
    )
    (comp (ref "V11")
      (value "V_SMD_FET_PMOS_SSM3J327R_20V_6A_4NC6_1W_SOT-23-3")
      (footprint "SMD_SOT_23_3")
      (fields (field (name "TYPE") "SSM3J327R"))
      (libsource (lib "AM") (part "V_SMD_FET_PMOS_SSM3J327R_20V_6A_4NC6_1W_SOT-23-3"))
    )
    (comp (ref "V12")
      (value "V_SMD_FET_PMOS_SSM3J327R_20V_6A_4NC6_1W_SOT-23-3")
      (footprint "SMD_SOT_23_3")
      (fields (field (name "TYPE") "SSM3J327R"))
      (libsource (lib "AM") (part "V_SMD_FET_PMOS_SSM3J327R_20V_6A_4NC6_1W_SOT-23-3"))
    )
    (comp (ref "V13")
      (value "V_SMD_SCHOTTKY_MBR0540T1G_40V_0A5_SOD-123")
      (footprint "SMD_SOD_123")
      (description "Schottky diode, 40V, 500mA, SOD-123")
      (fields (field (name "TYPE") "MBR0540T1G"))
      (libsource (lib "AM") (part "V_SMD_SCHOTTKY_MBR0540T1G_40V_0A5_SOD-123"))
    )
    (comp (ref "V14")
      (value "V_SMD_SCHOTTKY_MBR0540T1G_40V_0A5_SOD-123")
      (footprint "SMD_SOD_123")
      (description "Schottky diode, 40V, 500mA, SOD-123")
      (fields (field (name "TYPE") "MBR0540T1G"))
      (libsource (lib "AM") (part "V_SMD_SCHOTTKY_MBR0540T1G_40V_0A5_SOD-123"))
    )
    (comp (ref "V15")
      (value "V_SMD_SCHOTTKY_MBR0540T1G_40V_0A5_SOD-123")
      (footprint "SMD_SOD_123")
      (description "Schottky diode, 40V, 500mA, SOD-123")
      (fields (field (name "TYPE") "MBR0540T1G"))
      (libsource (lib "AM") (part "V_SMD_SCHOTTKY_MBR0540T1G_40V_0A5_SOD-123"))
    )
    (comp (ref "V16")
      (value "V_SMD_DIODE_RFUS20NS4STL_430V_20A_TO-263-3")
      (footprint "SMD_TO_263")
      (description "Super Fast Recovery Diode")
      (fields
        (field (name "TYPE") "RFUS20NS4STL")
        (field (name "ALTIUM_VALUE") "430V")
        (field (name "VALUE2") "20A")
      )
      (libsource (lib "AM") (part "V_SMD_DIODE_RFUS20NS4STL_430V_20A_TO-263-3"))
    )
    (comp (ref "V17")
      (value "V_THT_FET_NMOS_AOT11N60L_600V_11A_37NC_TO-220")
      (footprint "THT_TO_220")
      (description "600V, 11A N-Channel MOSFET")
      (fields (field (name "TYPE") "AOT11N60L"))
      (libsource (lib "AM") (part "V_THT_FET_NMOS_AOT11N60L_600V_11A_37NC_TO-220"))
    )
    (comp (ref "V18")
      (value "V_THT_FET_NMOS_AOT11N60L_600V_11A_37NC_TO-220")
      (footprint "THT_TO_220")
      (description "600V, 11A N-Channel MOSFET")
      (fields (field (name "TYPE") "AOT11N60L"))
      (libsource (lib "AM") (part "V_THT_FET_NMOS_AOT11N60L_600V_11A_37NC_TO-220"))
    )
    (comp (ref "V19")
      (value "V_THT_FET_NMOS_AOT11N60L_600V_11A_37NC_TO-220")
      (footprint "THT_TO_220")
      (description "600V, 11A N-Channel MOSFET")
      (fields (field (name "TYPE") "AOT11N60L"))
      (libsource (lib "AM") (part "V_THT_FET_NMOS_AOT11N60L_600V_11A_37NC_TO-220"))
    )
    (comp (ref "V20")
      (value "V_THT_FET_NMOS_AOT11N60L_600V_11A_37NC_TO-220")
      (footprint "THT_TO_220")
      (description "600V, 11A N-Channel MOSFET")
      (fields (field (name "TYPE") "AOT11N60L"))
      (libsource (lib "AM") (part "V_THT_FET_NMOS_AOT11N60L_600V_11A_37NC_TO-220"))
    )
    (comp (ref "V21")
      (value "V_SMD_FET_NMOS_FDN357N_30V_1A9_4NC2_0W5_SOT-23-3")
      (footprint "SMD_SOT_23_3")
      (description "N-Channel Logic Level Enhancement Mode Field Effect Transistor")
      (fields (field (name "TYPE") "FDN357N"))
      (libsource (lib "AM") (part "V_SMD_FET_NMOS_FDN357N_30V_1A9_4NC2_0W5_SOT-23-3"))
    )
    (comp (ref "X1")
      (value "X_CONNECTOR_P5.08_D1.5_1X2")
      (footprint "THT_CON_P5.08_D1.5_1X2")
      (description "Pitch 5.08, Diameter 1.5mm, 1 row, 2 columns")
      (libsource (lib "AM") (part "X_CONNECTOR_P5.08_D1.5_1X2"))
    )
    (comp (ref "X2")
      (value "X_CONNECTOR_P5.08_D1.5_1X2")
      (footprint "THT_CON_P5.08_D1.5_1X2")
      (description "Pitch 5.08, Diameter 1.5mm, 1 row, 2 columns")
      (libsource (lib "") (part "X_CONNECTOR_P5.08_D1.5_1X2_1"))
    )
    (comp (ref "X3")
      (value "X_CONNECTOR_P2.54_D0.9_1X6")
      (footprint "THT_CON_P2.54_D0.9_1X6")
      (description "Pitch 2.54, Diameter 0.9mm, 1 row, 6 columns")
      (libsource (lib "AM") (part "X_CONNECTOR_P2.54_D0.9_1X6"))
    )
    (comp (ref "Z1")
      (value "Z_SMD_FERRITE_1A5_470E@100MHZ_0603")
      (footprint "SMD_0603")
      (description "FERRITE CHIP 470 OHM 1500MA 0603")
      (libsource (lib "AM") (part "Z_SMD_FERRITE_1A5_470E@100MHZ_0603"))
    )
    (comp (ref "Z2")
      (value "Z_SMD_FERRITE_1A5_470E@100MHZ_0603")
      (footprint "SMD_0603")
      (description "FERRITE CHIP 470 OHM 1500MA 0603")
      (libsource (lib "AM") (part "Z_SMD_FERRITE_1A5_470E@100MHZ_0603"))
    )
    (comp (ref "Z3")
      (value "Z_SMD_FERRITE_1A5_470E@100MHZ_0603")
      (footprint "SMD_0603")
      (description "FERRITE CHIP 470 OHM 1500MA 0603")
      (libsource (lib "AM") (part "Z_SMD_FERRITE_1A5_470E@100MHZ_0603"))
    )
    (comp (ref "Z4")
      (value "Z_SMD_FERRITE_1A5_470E@100MHZ_0603")
      (footprint "SMD_0603")
      (description "FERRITE CHIP 470 OHM 1500MA 0603")
      (libsource (lib "AM") (part "Z_SMD_FERRITE_1A5_470E@100MHZ_0603"))
    )
    (comp (ref "Z5")
      (value "Z_SMD_FERRITE_1A5_470E@100MHZ_0603")
      (footprint "SMD_0603")
      (description "FERRITE CHIP 470 OHM 1500MA 0603")
      (libsource (lib "AM") (part "Z_SMD_FERRITE_1A5_470E@100MHZ_0603"))
    )
  )
  (nets
    (net (code "1") (name "+3.3V") (class "Default")
      (node (ref "C19") (pin "2") (pinfunction "2_2") (pintype "passive"))
      (node (ref "C2") (pin "1") (pinfunction "1_1") (pintype "passive"))
      (node (ref "C20") (pin "2") (pinfunction "2_2") (pintype "passive"))
      (node (ref "C22") (pin "2") (pinfunction "2_2") (pintype "passive"))
      (node (ref "C25") (pin "1") (pinfunction "1_1") (pintype "passive"))
      (node (ref "C3") (pin "2") (pinfunction "2_2") (pintype "passive"))
      (node (ref "L1") (pin "2") (pinfunction "2_2") (pintype "passive"))
      (node (ref "R11") (pin "2") (pinfunction "2_2") (pintype "passive"))
      (node (ref "R20") (pin "1") (pinfunction "1_1") (pintype "passive"))
      (node (ref "R4") (pin "2") (pinfunction "2_2") (pintype "passive"))
      (node (ref "V10") (pin "1") (pinfunction "1_1") (pintype "passive"))
      (node (ref "X3") (pin "2") (pinfunction "2_2") (pintype "passive"))
      (node (ref "Z1") (pin "2") (pinfunction "2_2") (pintype "passive"))
      (node (ref "Z2") (pin "2") (pinfunction "2_2") (pintype "passive"))
      (node (ref "Z3") (pin "2") (pinfunction "2_2") (pintype "passive"))
      (node (ref "Z4") (pin "1") (pinfunction "1_1") (pintype "passive"))
      (node (ref "Z5") (pin "1") (pinfunction "1_1") (pintype "passive"))
    )
    (net (code "2") (name "+12V") (class "Default")
      (node (ref "C18") (pin "2") (pinfunction "2_2") (pintype "passive"))
      (node (ref "C6") (pin "2") (pinfunction "2_2") (pintype "passive"))
      (node (ref "C7") (pin "2") (pinfunction "2_2") (pintype "passive"))
      (node (ref "C8") (pin "2") (pinfunction "2_2") (pintype "passive"))
      (node (ref "C9") (pin "2") (pinfunction "2_2") (pintype "passive"))
      (node (ref "D2") (pin "1") (pinfunction "VCC_1") (pintype "passive"))
      (node (ref "D3") (pin "1") (pinfunction "VCC_1") (pintype "passive"))
      (node (ref "H2") (pin "6") (pinfunction "Vcc_6") (pintype "passive"))
      (node (ref "H3") (pin "6") (pinfunction "Vcc_6") (pintype "passive"))
      (node (ref "H4") (pin "6") (pinfunction "Vcc_6") (pintype "passive"))
      (node (ref "H5") (pin "6") (pinfunction "Vcc_6") (pintype "passive"))
      (node (ref "N2") (pin "3") (pinfunction "+_3") (pintype "passive"))
      (node (ref "R12") (pin "2") (pinfunction "2_2") (pintype "passive"))
      (node (ref "R14") (pin "2") (pinfunction "2_2") (pintype "passive"))
      (node (ref "R16") (pin "1") (pinfunction "1_1") (pintype "passive"))
      (node (ref "R26") (pin "2") (pinfunction "2_2") (pintype "passive"))
      (node (ref "R27") (pin "2") (pinfunction "2_2") (pintype "passive"))
      (node (ref "R8") (pin "2") (pinfunction "2_2") (pintype "passive"))
      (node (ref "V11") (pin "2") (pinfunction "Source_2") (pintype "passive"))
      (node (ref "V12") (pin "2") (pinfunction "Source_2") (pintype "passive"))
      (node (ref "V14") (pin "1") (pinfunction "1_1") (pintype "passive"))
      (node (ref "V15") (pin "1") (pinfunction "1_1") (pintype "passive"))
      (node (ref "V3") (pin "2") (pinfunction "2_2") (pintype "passive"))
      (node (ref "V6") (pin "3") (pinfunction "Source_3") (pintype "passive"))
    )
    (net (code "3") (name "+325V") (class "Default")
      (node (ref "C14") (pin "2") (pinfunction "2_2") (pintype "passive"))
      (node (ref "C15") (pin "2") (pinfunction "2_2") (pintype "passive"))
      (node (ref "R1") (pin "2") (pinfunction "2_2") (pintype "passive"))
      (node (ref "R3") (pin "2") (pinfunction "2_2") (pintype "passive"))
      (node (ref "R33") (pin "2") (pinfunction "2_2") (pintype "passive"))
      (node (ref "V4") (pin "2") (pinfunction "2_2") (pintype "passive"))
      (node (ref "V5") (pin "2") (pinfunction "Drain_2") (pintype "passive"))
      (node (ref "V7") (pin "3") (pinfunction "Source_3") (pintype "passive"))
    )
    (net (code "4") (name "/HBRDG_H") (class "Default")
      (node (ref "D1") (pin "54") (pinfunction "PWM5L/CN15/RD6_54") (pintype "passive"))
      (node (ref "R23") (pin "1") (pinfunction "1_1") (pintype "passive"))
    )
    (net (code "5") (name "/HBRDG_L") (class "Default")
      (node (ref "D1") (pin "55") (pinfunction "PWM5H/UPDN1/CN16/RD7_55") (pintype "passive"))
      (node (ref "R25") (pin "1") (pinfunction "1_1") (pintype "passive"))
    )
    (net (code "6") (name "/OUT_12V") (class "Default")
      (node (ref "D1") (pin "59") (pinfunction "RF1_59") (pintype "passive"))
      (node (ref "R22") (pin "2") (pinfunction "2_2") (pintype "passive"))
    )
    (net (code "7") (name "/OUT_325V") (class "Default")
      (node (ref "D1") (pin "58") (pinfunction "SYNCI4/RF0_58") (pintype "passive"))
      (node (ref "R24") (pin "2") (pinfunction "2_2") (pintype "passive"))
    )
    (net (code "8") (name "/PGEC") (class "Default")
      (node (ref "D1") (pin "17") (pinfunction "PGEC1/AN6/OCFA/RB6_17") (pintype "passive"))
      (node (ref "X3") (pin "5") (pinfunction "5_5") (pintype "passive"))
    )
    (net (code "9") (name "/PGED") (class "Default")
      (node (ref "D1") (pin "18") (pinfunction "PGED1/AN7/RB7_18") (pintype "passive"))
      (node (ref "X3") (pin "4") (pinfunction "4_4") (pintype "passive"))
    )
    (net (code "10") (name "FBR_RD") (class "Default")
      (node (ref "D1") (pin "31") (pinfunction "U2RX/SDA2/FLT17/CN17/RF4_31") (pintype "passive"))
      (node (ref "H1") (pin "2") (pinfunction "RD_2") (pintype "passive"))
    )
    (net (code "11") (name "FBR_SD") (class "Default")
      (node (ref "D1") (pin "35") (pinfunction "_U1RTS/SCK1/INT0/RF6_35") (pintype "passive"))
      (node (ref "H1") (pin "4") (pinfunction "SD_4") (pintype "passive"))
    )
    (net (code "12") (name "FBR_TD") (class "Default")
      (node (ref "D1") (pin "32") (pinfunction "U2TX/SCL2/FLT18/CN18/RF5_32") (pintype "passive"))
      (node (ref "N1") (pin "2") (pinfunction "+_2") (pintype "passive"))
    )
    (net (code "13") (name "GND") (class "Default")
      (node (ref "C1") (pin "1") (pinfunction "1_1") (pintype "passive"))
      (node (ref "C10") (pin "1") (pinfunction "1_1") (pintype "passive"))
      (node (ref "C11") (pin "1") (pinfunction "1_1") (pintype "passive"))
      (node (ref "C12") (pin "1") (pinfunction "1_1") (pintype "passive"))
      (node (ref "C13") (pin "1") (pinfunction "1_1") (pintype "passive"))
      (node (ref "C19") (pin "1") (pinfunction "1_1") (pintype "passive"))
      (node (ref "C2") (pin "2") (pinfunction "2_2") (pintype "passive"))
      (node (ref "C20") (pin "1") (pinfunction "1_1") (pintype "passive"))
      (node (ref "C22") (pin "1") (pinfunction "1_1") (pintype "passive"))
      (node (ref "C24") (pin "1") (pinfunction "1_1") (pintype "passive"))
      (node (ref "C28") (pin "1") (pinfunction "1_1") (pintype "passive"))
      (node (ref "C29") (pin "1") (pinfunction "1_1") (pintype "passive"))
      (node (ref "C3") (pin "1") (pinfunction "1_1") (pintype "passive"))
      (node (ref "C30") (pin "1") (pinfunction "1_1") (pintype "passive"))
      (node (ref "C31") (pin "1") (pinfunction "1_1") (pintype "passive"))
      (node (ref "C32") (pin "1") (pinfunction "1_1") (pintype "passive"))
      (node (ref "C33") (pin "1") (pinfunction "1_1") (pintype "passive"))
      (node (ref "C4") (pin "1") (pinfunction "1_1") (pintype "passive"))
      (node (ref "C5") (pin "2") (pinfunction "2_2") (pintype "passive"))
      (node (ref "D1") (pin "20") (pinfunction "AVSS_20") (pintype "passive"))
      (node (ref "D1") (pin "25") (pinfunction "VSS_25") (pintype "passive"))
      (node (ref "D1") (pin "41") (pinfunction "VSS_41") (pintype "passive"))
      (node (ref "D1") (pin "9") (pinfunction "VSS_9") (pintype "passive"))
      (node (ref "H1") (pin "1") (pinfunction "Vee_1") (pintype "passive"))
      (node (ref "H1") (pin "9") (pinfunction "Vee_9") (pintype "passive"))
      (node (ref "H2") (pin "2") (pinfunction "Cathode_2") (pintype "passive"))
      (node (ref "H3") (pin "2") (pinfunction "Cathode_2") (pintype "passive"))
      (node (ref "H4") (pin "2") (pinfunction "Cathode_2") (pintype "passive"))
      (node (ref "H5") (pin "2") (pinfunction "Cathode_2") (pintype "passive"))
      (node (ref "N1") (pin "4") (pinfunction "V-_4") (pintype "passive"))
      (node (ref "N1") (pin "5") (pinfunction "LATCH_ENABLE_5") (pintype "passive"))
      (node (ref "N1") (pin "6") (pinfunction "GND_6") (pintype "passive"))
      (node (ref "N3") (pin "2") (pinfunction "GND_2") (pintype "passive"))
      (node (ref "N5") (pin "4") (pinfunction "-_4") (pintype "passive"))
      (node (ref "R21") (pin "2") (pinfunction "2_2") (pintype "passive"))
      (node (ref "R5") (pin "1") (pinfunction "1_1") (pintype "passive"))
      (node (ref "V13") (pin "1") (pinfunction "1_1") (pintype "passive"))
      (node (ref "X3") (pin "3") (pinfunction "3_3") (pintype "passive"))
    )
    (net (code "14") (name "Net-(C4-Pad2)") (class "Default")
      (node (ref "C4") (pin "2") (pinfunction "2_2") (pintype "passive"))
      (node (ref "H1") (pin "6") (pinfunction "Vcc_6") (pintype "passive"))
      (node (ref "Z3") (pin "1") (pinfunction "1_1") (pintype "passive"))
    )
    (net (code "15") (name "Net-(C5-Pad1)") (class "Default")
      (node (ref "C5") (pin "1") (pinfunction "1_1") (pintype "passive"))
      (node (ref "H1") (pin "5") (pinfunction "Vcc_5") (pintype "passive"))
      (node (ref "Z2") (pin "1") (pinfunction "1_1") (pintype "passive"))
    )
    (net (code "16") (name "Net-(C10-Pad2)") (class "Default")
      (node (ref "C10") (pin "2") (pinfunction "2_2") (pintype "passive"))
      (node (ref "C11") (pin "2") (pinfunction "2_2") (pintype "passive"))
      (node (ref "C12") (pin "2") (pinfunction "2_2") (pintype "passive"))
      (node (ref "C28") (pin "2") (pinfunction "2_2") (pintype "passive"))
      (node (ref "C29") (pin "2") (pinfunction "2_2") (pintype "passive"))
      (node (ref "C30") (pin "2") (pinfunction "2_2") (pintype "passive"))
      (node (ref "C31") (pin "2") (pinfunction "2_2") (pintype "passive"))
      (node (ref "D1") (pin "10") (pinfunction "VDD_10") (pintype "passive"))
      (node (ref "D1") (pin "26") (pinfunction "VDD_26") (pintype "passive"))
      (node (ref "D1") (pin "38") (pinfunction "VDD_38") (pintype "passive"))
      (node (ref "D1") (pin "57") (pinfunction "VDD_57") (pintype "passive"))
      (node (ref "Z4") (pin "2") (pinfunction "2_2") (pintype "passive"))
    )
    (net (code "17") (name "Net-(C23-Pad2)") (class "Default")
      (node (ref "C23") (pin "2") (pinfunction "2_2") (pintype "passive"))
      (node (ref "N4") (pin "1") (pinfunction "1_1") (pintype "passive"))
      (node (ref "R12") (pin "1") (pinfunction "1_1") (pintype "passive"))
      (node (ref "R13") (pin "2") (pinfunction "2_2") (pintype "passive"))
    )
    (net (code "18") (name "Net-(D1-AVDD)") (class "Default")
      (node (ref "C13") (pin "2") (pinfunction "2_2") (pintype "passive"))
      (node (ref "C32") (pin "2") (pinfunction "2_2") (pintype "passive"))
      (node (ref "D1") (pin "19") (pinfunction "AVDD_19") (pintype "passive"))
      (node (ref "Z5") (pin "2") (pinfunction "2_2") (pintype "passive"))
    )
    (net (code "19") (name "Net-(D1-VCAP)") (class "Default")
      (node (ref "C33") (pin "2") (pinfunction "2_2") (pintype "passive"))
      (node (ref "D1") (pin "56") (pinfunction "VCAP_56") (pintype "passive"))
    )
    (net (code "20") (name "Net-(D1-_MCLR)") (class "Default")
      (node (ref "D1") (pin "7") (pinfunction "_MCLR_7") (pintype "passive"))
      (node (ref "R32") (pin "1") (pinfunction "1_1") (pintype "passive"))
    )
    (net (code "21") (name "Net-(D2-HO)") (class "Default")
      (node (ref "D2") (pin "7") (pinfunction "HO_7") (pintype "passive"))
      (node (ref "R28") (pin "1") (pinfunction "1_1") (pintype "passive"))
    )
    (net (code "22") (name "Net-(D2-IN)") (class "Default")
      (node (ref "D2") (pin "2") (pinfunction "IN_2") (pintype "passive"))
      (node (ref "H3") (pin "4") (pinfunction "Vo_4") (pintype "passive"))
      (node (ref "R26") (pin "1") (pinfunction "1_1") (pintype "passive"))
    )
    (net (code "23") (name "Net-(D2-LO)") (class "Default")
      (node (ref "D2") (pin "5") (pinfunction "LO_5") (pintype "passive"))
      (node (ref "R29") (pin "1") (pinfunction "1_1") (pintype "passive"))
    )
    (net (code "24") (name "Net-(D2-VB)") (class "Default")
      (node (ref "C26") (pin "1") (pinfunction "1_1") (pintype "passive"))
      (node (ref "D2") (pin "8") (pinfunction "VB_8") (pintype "passive"))
      (node (ref "V14") (pin "2") (pinfunction "2_2") (pintype "passive"))
    )
    (net (code "25") (name "Net-(D2-VS)") (class "Default")
      (node (ref "C26") (pin "2") (pinfunction "2_2") (pintype "passive"))
      (node (ref "D2") (pin "6") (pinfunction "VS_6") (pintype "passive"))
      (node (ref "V17") (pin "3") (pinfunction "Source_3") (pintype "passive"))
      (node (ref "V18") (pin "2") (pinfunction "Drain_2") (pintype "passive"))
      (node (ref "X2") (pin "1") (pinfunction "1_1") (pintype "passive"))
    )
    (net (code "26") (name "Net-(D3-HO)") (class "Default")
      (node (ref "D3") (pin "7") (pinfunction "HO_7") (pintype "passive"))
      (node (ref "R30") (pin "1") (pinfunction "1_1") (pintype "passive"))
    )
    (net (code "27") (name "Net-(D3-IN)") (class "Default")
      (node (ref "D3") (pin "2") (pinfunction "IN_2") (pintype "passive"))
      (node (ref "H5") (pin "4") (pinfunction "Vo_4") (pintype "passive"))
      (node (ref "R27") (pin "1") (pinfunction "1_1") (pintype "passive"))
    )
    (net (code "28") (name "Net-(D3-LO)") (class "Default")
      (node (ref "D3") (pin "5") (pinfunction "LO_5") (pintype "passive"))
      (node (ref "R31") (pin "1") (pinfunction "1_1") (pintype "passive"))
    )
    (net (code "29") (name "Net-(D3-VB)") (class "Default")
      (node (ref "C27") (pin "1") (pinfunction "1_1") (pintype "passive"))
      (node (ref "D3") (pin "8") (pinfunction "VB_8") (pintype "passive"))
      (node (ref "V15") (pin "2") (pinfunction "2_2") (pintype "passive"))
    )
    (net (code "30") (name "Net-(D3-VS)") (class "Default")
      (node (ref "C27") (pin "2") (pinfunction "2_2") (pintype "passive"))
      (node (ref "D3") (pin "6") (pinfunction "VS_6") (pintype "passive"))
      (node (ref "V19") (pin "3") (pinfunction "Source_3") (pintype "passive"))
      (node (ref "V20") (pin "2") (pinfunction "Drain_2") (pintype "passive"))
      (node (ref "X2") (pin "2") (pinfunction "2_2") (pintype "passive"))
    )
    (net (code "31") (name "Net-(H1-TD)") (class "Default")
      (node (ref "H1") (pin "8") (pinfunction "TD_8") (pintype "passive"))
      (node (ref "N1") (pin "7") (pinfunction "Q_7") (pintype "passive"))
    )
    (net (code "32") (name "Net-(H1-{slash}TD)") (class "Default")
      (node (ref "H1") (pin "7") (pinfunction "/TD_7") (pintype "passive"))
      (node (ref "N1") (pin "8") (pinfunction "/Q_8") (pintype "passive"))
    )
    (net (code "33") (name "Net-(H2-Anode)") (class "Default")
      (node (ref "H2") (pin "1") (pinfunction "Anode_1") (pintype "passive"))
      (node (ref "R22") (pin "1") (pinfunction "1_1") (pintype "passive"))
    )
    (net (code "34") (name "Net-(H2-Vo)") (class "Default")
      (node (ref "H2") (pin "4") (pinfunction "Vo_4") (pintype "passive"))
      (node (ref "R15") (pin "2") (pinfunction "2_2") (pintype "passive"))
    )
    (net (code "35") (name "Net-(H3-Anode)") (class "Default")
      (node (ref "H3") (pin "1") (pinfunction "Anode_1") (pintype "passive"))
      (node (ref "R23") (pin "2") (pinfunction "2_2") (pintype "passive"))
    )
    (net (code "36") (name "Net-(H4-Anode)") (class "Default")
      (node (ref "H4") (pin "1") (pinfunction "Anode_1") (pintype "passive"))
      (node (ref "R24") (pin "1") (pinfunction "1_1") (pintype "passive"))
    )
    (net (code "37") (name "Net-(H4-Vo)") (class "Default")
      (node (ref "H4") (pin "4") (pinfunction "Vo_4") (pintype "passive"))
      (node (ref "R18") (pin "2") (pinfunction "2_2") (pintype "passive"))
    )
    (net (code "38") (name "Net-(H5-Anode)") (class "Default")
      (node (ref "H5") (pin "1") (pinfunction "Anode_1") (pintype "passive"))
      (node (ref "R25") (pin "2") (pinfunction "2_2") (pintype "passive"))
    )
    (net (code "39") (name "Net-(N1--)") (class "Default")
      (node (ref "N1") (pin "3") (pinfunction "-_3") (pintype "passive"))
      (node (ref "R4") (pin "1") (pinfunction "1_1") (pintype "passive"))
      (node (ref "R5") (pin "2") (pinfunction "2_2") (pintype "passive"))
    )
    (net (code "40") (name "Net-(N1-V+)") (class "Default")
      (node (ref "C1") (pin "2") (pinfunction "2_2") (pintype "passive"))
      (node (ref "N1") (pin "1") (pinfunction "V+_1") (pintype "passive"))
      (node (ref "Z1") (pin "1") (pinfunction "1_1") (pintype "passive"))
    )
    (net (code "41") (name "Net-(N2-~-Pad1)") (class "Default")
      (node (ref "N2") (pin "1") (pinfunction "~_1") (pintype "passive"))
      (node (ref "N5") (pin "1") (pinfunction "~_1") (pintype "passive"))
      (node (ref "V1") (pin "2") (pinfunction "2_2") (pintype "passive"))
      (node (ref "X1") (pin "1") (pinfunction "1_1") (pintype "passive"))
    )
    (net (code "42") (name "Net-(N2-~-Pad2)") (class "Default")
      (node (ref "N2") (pin "2") (pinfunction "~_2") (pintype "passive"))
      (node (ref "N5") (pin "2") (pinfunction "~_2") (pintype "passive"))
      (node (ref "V1") (pin "3") (pinfunction "3_3") (pintype "passive"))
      (node (ref "X1") (pin "2") (pinfunction "2_2") (pintype "passive"))
    )
    (net (code "43") (name "Net-(N3-BOOST)") (class "Default")
      (node (ref "C21") (pin "2") (pinfunction "2_2") (pintype "passive"))
      (node (ref "N3") (pin "1") (pinfunction "BOOST_1") (pintype "passive"))
      (node (ref "V10") (pin "2") (pinfunction "2_2") (pintype "passive"))
    )
    (net (code "44") (name "Net-(N3-FB)") (class "Default")
      (node (ref "C25") (pin "2") (pinfunction "2_2") (pintype "passive"))
      (node (ref "N3") (pin "3") (pinfunction "FB_3") (pintype "passive"))
      (node (ref "R20") (pin "2") (pinfunction "2_2") (pintype "passive"))
      (node (ref "R21") (pin "1") (pinfunction "1_1") (pintype "passive"))
    )
    (net (code "45") (name "Net-(N3-SW)") (class "Default")
      (node (ref "C21") (pin "1") (pinfunction "1_1") (pintype "passive"))
      (node (ref "L1") (pin "1") (pinfunction "1_1") (pintype "passive"))
      (node (ref "N3") (pin "6") (pinfunction "SW_6") (pintype "passive"))
      (node (ref "V13") (pin "2") (pinfunction "2_2") (pintype "passive"))
    )
    (net (code "46") (name "Net-(N3-Vin)") (class "Default")
      (node (ref "C24") (pin "2") (pinfunction "2_2") (pintype "passive"))
      (node (ref "N3") (pin "4") (pinfunction "/SHDN_4") (pintype "passive"))
      (node (ref "N3") (pin "5") (pinfunction "Vin_5") (pintype "passive"))
      (node (ref "N5") (pin "3") (pinfunction "+_3") (pintype "passive"))
    )
    (net (code "47") (name "Net-(V5-Gate)") (class "Default")
      (node (ref "R2") (pin "1") (pinfunction "1_1") (pintype "passive"))
      (node (ref "R6") (pin "2") (pinfunction "2_2") (pintype "passive"))
      (node (ref "V2") (pin "1") (pinfunction "1_1") (pintype "passive"))
      (node (ref "V5") (pin "1") (pinfunction "Gate_1") (pintype "passive"))
    )
    (net (code "48") (name "Net-(V5-Source)") (class "Default")
      (node (ref "R1") (pin "1") (pinfunction "1_1") (pintype "passive"))
      (node (ref "R2") (pin "2") (pinfunction "2_2") (pintype "passive"))
      (node (ref "V1") (pin "1") (pinfunction "1_1") (pintype "passive"))
      (node (ref "V2") (pin "2") (pinfunction "2_2") (pintype "passive"))
      (node (ref "V5") (pin "3") (pinfunction "Source_3") (pintype "passive"))
    )
    (net (code "49") (name "Net-(V6-Drain)") (class "Default")
      (node (ref "V16") (pin "1") (pinfunction "1_1") (pintype "passive"))
      (node (ref "V16") (pin "3") (pinfunction "3_3") (pintype "passive"))
      (node (ref "V6") (pin "2") (pinfunction "Drain_2") (pintype "passive"))
    )
    (net (code "50") (name "Net-(V6-Gate)") (class "Default")
      (node (ref "R14") (pin "1") (pinfunction "1_1") (pintype "passive"))
      (node (ref "R15") (pin "1") (pinfunction "1_1") (pintype "passive"))
      (node (ref "V3") (pin "1") (pinfunction "1_1") (pintype "passive"))
      (node (ref "V6") (pin "1") (pinfunction "Gate_1") (pintype "passive"))
    )
    (net (code "51") (name "Net-(V7-Gate)") (class "Default")
      (node (ref "R3") (pin "1") (pinfunction "1_1") (pintype "passive"))
      (node (ref "R7") (pin "1") (pinfunction "1_1") (pintype "passive"))
      (node (ref "V4") (pin "1") (pinfunction "1_1") (pintype "passive"))
      (node (ref "V7") (pin "1") (pinfunction "Gate_1") (pintype "passive"))
    )
    (net (code "52") (name "Net-(V8-Drain)") (class "Default")
      (node (ref "R6") (pin "1") (pinfunction "1_1") (pintype "passive"))
      (node (ref "V8") (pin "3") (pinfunction "Drain_3") (pintype "passive"))
    )
    (net (code "53") (name "Net-(V9-Drain)") (class "Default")
      (node (ref "R7") (pin "2") (pinfunction "2_2") (pintype "passive"))
      (node (ref "V9") (pin "3") (pinfunction "Drain_3") (pintype "passive"))
    )
    (net (code "54") (name "Net-(V11-Gate)") (class "Default")
      (node (ref "R8") (pin "1") (pinfunction "1_1") (pintype "passive"))
      (node (ref "R9") (pin "2") (pinfunction "2_2") (pintype "passive"))
      (node (ref "V11") (pin "1") (pinfunction "Gate_1") (pintype "passive"))
    )
    (net (code "55") (name "Net-(V12-Drain)") (class "Default")
      (node (ref "R17") (pin "2") (pinfunction "2_2") (pintype "passive"))
      (node (ref "V12") (pin "3") (pinfunction "Drain_3") (pintype "passive"))
    )
    (net (code "56") (name "Net-(V12-Gate)") (class "Default")
      (node (ref "R16") (pin "2") (pinfunction "2_2") (pintype "passive"))
      (node (ref "R18") (pin "1") (pinfunction "1_1") (pintype "passive"))
      (node (ref "V12") (pin "1") (pinfunction "Gate_1") (pintype "passive"))
    )
    (net (code "57") (name "Net-(V17-Gate)") (class "Default")
      (node (ref "R28") (pin "2") (pinfunction "2_2") (pintype "passive"))
      (node (ref "V17") (pin "1") (pinfunction "Gate_1") (pintype "passive"))
    )
    (net (code "58") (name "Net-(V18-Gate)") (class "Default")
      (node (ref "R29") (pin "2") (pinfunction "2_2") (pintype "passive"))
      (node (ref "V18") (pin "1") (pinfunction "Gate_1") (pintype "passive"))
    )
    (net (code "59") (name "Net-(V19-Gate)") (class "Default")
      (node (ref "R30") (pin "2") (pinfunction "2_2") (pintype "passive"))
      (node (ref "V19") (pin "1") (pinfunction "Gate_1") (pintype "passive"))
    )
    (net (code "60") (name "Net-(V20-Gate)") (class "Default")
      (node (ref "R31") (pin "2") (pinfunction "2_2") (pintype "passive"))
      (node (ref "V20") (pin "1") (pinfunction "Gate_1") (pintype "passive"))
    )
    (net (code "61") (name "Net-(V21-Drain)") (class "Default")
      (node (ref "R17") (pin "1") (pinfunction "1_1") (pintype "passive"))
      (node (ref "R19") (pin "1") (pinfunction "1_1") (pintype "passive"))
      (node (ref "V21") (pin "3") (pinfunction "Drain_3") (pintype "passive"))
      (node (ref "V9") (pin "1") (pinfunction "Gate_1") (pintype "passive"))
    )
    (net (code "62") (name "PB") (class "Default")
      (node (ref "N4") (pin "2") (pinfunction "2_2") (pintype "passive"))
      (node (ref "R9") (pin "1") (pinfunction "1_1") (pintype "passive"))
      (node (ref "V21") (pin "1") (pinfunction "Gate_1") (pintype "passive"))
    )
    (net (code "63") (name "PG") (class "Default")
      (node (ref "D2") (pin "3") (pinfunction "/SD_3") (pintype "passive"))
      (node (ref "D3") (pin "3") (pinfunction "/SD_3") (pintype "passive"))
      (node (ref "R10") (pin "2") (pinfunction "2_2") (pintype "passive"))
      (node (ref "V11") (pin "3") (pinfunction "Drain_3") (pintype "passive"))
      (node (ref "V8") (pin "1") (pinfunction "Gate_1") (pintype "passive"))
    )
    (net (code "64") (name "PGND") (class "Default")
      (node (ref "C14") (pin "1") (pinfunction "1_1") (pintype "passive"))
      (node (ref "C15") (pin "1") (pinfunction "1_1") (pintype "passive"))
      (node (ref "C16") (pin "1") (pinfunction "1_1") (pintype "passive"))
      (node (ref "C17") (pin "1") (pinfunction "1_1") (pintype "passive"))
      (node (ref "C18") (pin "1") (pinfunction "1_1") (pintype "passive"))
      (node (ref "C23") (pin "1") (pinfunction "1_1") (pintype "passive"))
      (node (ref "C6") (pin "1") (pinfunction "1_1") (pintype "passive"))
      (node (ref "C7") (pin "1") (pinfunction "1_1") (pintype "passive"))
      (node (ref "C8") (pin "1") (pinfunction "1_1") (pintype "passive"))
      (node (ref "C9") (pin "1") (pinfunction "1_1") (pintype "passive"))
      (node (ref "D2") (pin "4") (pinfunction "COM_4") (pintype "passive"))
      (node (ref "D3") (pin "4") (pinfunction "COM_4") (pintype "passive"))
      (node (ref "H2") (pin "5") (pinfunction "GND_5") (pintype "passive"))
      (node (ref "H3") (pin "5") (pinfunction "GND_5") (pintype "passive"))
      (node (ref "H4") (pin "5") (pinfunction "GND_5") (pintype "passive"))
      (node (ref "H5") (pin "5") (pinfunction "GND_5") (pintype "passive"))
      (node (ref "N2") (pin "4") (pinfunction "-_4") (pintype "passive"))
      (node (ref "N4") (pin "3") (pinfunction "3_3") (pintype "passive"))
      (node (ref "R10") (pin "1") (pinfunction "1_1") (pintype "passive"))
      (node (ref "R13") (pin "1") (pinfunction "1_1") (pintype "passive"))
      (node (ref "R19") (pin "2") (pinfunction "2_2") (pintype "passive"))
      (node (ref "R33") (pin "1") (pinfunction "1_1") (pintype "passive"))
      (node (ref "V1") (pin "4") (pinfunction "4_4") (pintype "passive"))
      (node (ref "V18") (pin "3") (pinfunction "Source_3") (pintype "passive"))
      (node (ref "V20") (pin "3") (pinfunction "Source_3") (pintype "passive"))
      (node (ref "V21") (pin "2") (pinfunction "Source_2") (pintype "passive"))
      (node (ref "V8") (pin "2") (pinfunction "Source_2") (pintype "passive"))
      (node (ref "V9") (pin "2") (pinfunction "Source_2") (pintype "passive"))
    )
    (net (code "65") (name "VHBRDG") (class "Default")
      (node (ref "C16") (pin "2") (pinfunction "2_2") (pintype "passive"))
      (node (ref "C17") (pin "2") (pinfunction "2_2") (pintype "passive"))
      (node (ref "V16") (pin "2") (pinfunction "2_2") (pintype "passive"))
      (node (ref "V17") (pin "2") (pinfunction "Drain_2") (pintype "passive"))
      (node (ref "V19") (pin "2") (pinfunction "Drain_2") (pintype "passive"))
      (node (ref "V7") (pin "2") (pinfunction "Drain_2") (pintype "passive"))
    )
    (net (code "66") (name "unconnected-(C14-Pad3)") (class "Default")
      (node (ref "C14") (pin "3") (pinfunction "3_3") (pintype "passive"))
    )
    (net (code "67") (name "unconnected-(C14-Pad4)") (class "Default")
      (node (ref "C14") (pin "4") (pinfunction "4_4") (pintype "passive"))
    )
    (net (code "68") (name "unconnected-(D1-AN2{slash}_ASS1{slash}CN4{slash}RB2-Pad14)") (class "Default")
      (node (ref "D1") (pin "14") (pinfunction "AN2/_ASS1/CN4/RB2_14") (pintype "passive"))
    )
    (net (code "69") (name "unconnected-(D1-AN3{slash}AINDX1{slash}CN5{slash}RB3-Pad13)") (class "Default")
      (node (ref "D1") (pin "13") (pinfunction "AN3/AINDX1/CN5/RB3_13") (pintype "passive"))
    )
    (net (code "70") (name "unconnected-(D1-AN4{slash}AQEA1{slash}CN6{slash}RB4-Pad12)") (class "Default")
      (node (ref "D1") (pin "12") (pinfunction "AN4/AQEA1/CN6/RB4_12") (pintype "passive"))
    )
    (net (code "71") (name "unconnected-(D1-AN5{slash}AQEB1{slash}CN7{slash}RB5-Pad11)") (class "Default")
      (node (ref "D1") (pin "11") (pinfunction "AN5/AQEB1/CN7/RB5_11") (pintype "passive"))
    )
    (net (code "72") (name "unconnected-(D1-AN8{slash}_U2CTS{slash}RB8-Pad21)") (class "Default")
      (node (ref "D1") (pin "21") (pinfunction "AN8/_U2CTS/RB8_21") (pintype "passive"))
    )
    (net (code "73") (name "unconnected-(D1-AN9{slash}RB9-Pad22)") (class "Default")
      (node (ref "D1") (pin "22") (pinfunction "AN9/RB9_22") (pintype "passive"))
    )
    (net (code "74") (name "unconnected-(D1-AN14{slash}_SS1{slash}_U2RTS{slash}RB14-Pad29)") (class "Default")
      (node (ref "D1") (pin "29") (pinfunction "AN14/_SS1/_U2RTS/RB14_29") (pintype "passive"))
    )
    (net (code "75") (name "unconnected-(D1-AN15{slash}CN12{slash}RB15-Pad30)") (class "Default")
      (node (ref "D1") (pin "30") (pinfunction "AN15/CN12/RB15_30") (pintype "passive"))
    )
    (net (code "76") (name "unconnected-(D1-IC1{slash}FLT1{slash}SYNCI1{slash}INT1{slash}RD8-Pad42)") (class "Default")
      (node (ref "D1") (pin "42") (pinfunction "IC1/FLT1/SYNCI1/INT1/RD8_42") (pintype "passive"))
    )
    (net (code "77") (name "unconnected-(D1-IC2{slash}FLT2{slash}_U1CTS{slash}INT2{slash}RD9-Pad43)") (class "Default")
      (node (ref "D1") (pin "43") (pinfunction "IC2/FLT2/_U1CTS/INT2/RD9_43") (pintype "passive"))
    )
    (net (code "78") (name "unconnected-(D1-IC3{slash}INDX1{slash}FLT3{slash}INT3{slash}RD10-Pad44)") (class "Default")
      (node (ref "D1") (pin "44") (pinfunction "IC3/INDX1/FLT3/INT3/RD10_44") (pintype "passive"))
    )
    (net (code "79") (name "unconnected-(D1-IC4{slash}QEA1{slash}FLT4{slash}INT4{slash}RD11-Pad45)") (class "Default")
      (node (ref "D1") (pin "45") (pinfunction "IC4/QEA1/FLT4/INT4/RD11_45") (pintype "passive"))
    )
    (net (code "80") (name "unconnected-(D1-OC1{slash}QEB1{slash}FLT5{slash}RD0-Pad46)") (class "Default")
      (node (ref "D1") (pin "46") (pinfunction "OC1/QEB1/FLT5/RD0_46") (pintype "passive"))
    )
    (net (code "81") (name "unconnected-(D1-OC2{slash}SYNCO2{slash}FLT6{slash}RD1-Pad49)") (class "Default")
      (node (ref "D1") (pin "49") (pinfunction "OC2/SYNCO2/FLT6/RD1_49") (pintype "passive"))
    )
    (net (code "82") (name "unconnected-(D1-OC3{slash}FLT7{slash}RD2-Pad50)") (class "Default")
      (node (ref "D1") (pin "50") (pinfunction "OC3/FLT7/RD2_50") (pintype "passive"))
    )
    (net (code "83") (name "unconnected-(D1-OC4{slash}SYNCO1{slash}RD3-Pad51)") (class "Default")
      (node (ref "D1") (pin "51") (pinfunction "OC4/SYNCO1/RD3_51") (pintype "passive"))
    )
    (net (code "84") (name "unconnected-(D1-OSC1{slash}CLKIN{slash}RC12-Pad39)") (class "Default")
      (node (ref "D1") (pin "39") (pinfunction "OSC1/CLKIN/RC12_39") (pintype "passive"))
    )
    (net (code "85") (name "unconnected-(D1-OSC2{slash}REFCLKO{slash}CLKO{slash}RC15-Pad40)") (class "Default")
      (node (ref "D1") (pin "40") (pinfunction "OSC2/REFCLKO/CLKO/RC15_40") (pintype "passive"))
    )
    (net (code "86") (name "unconnected-(D1-PGEC2{slash}SOSCO{slash}T1CK{slash}CN0{slash}RC14-Pad48)") (class "Default")
      (node (ref "D1") (pin "48") (pinfunction "PGEC2/SOSCO/T1CK/CN0/RC14_48") (pintype "passive"))
    )
    (net (code "87") (name "unconnected-(D1-PGEC3{slash}AN1{slash}CN3{slash}RB1-Pad15)") (class "Default")
      (node (ref "D1") (pin "15") (pinfunction "PGEC3/AN1/CN3/RB1_15") (pintype "passive"))
    )
    (net (code "88") (name "unconnected-(D1-PGED2{slash}SOSCI{slash}T4CK{slash}CN1{slash}RC13-Pad47)") (class "Default")
      (node (ref "D1") (pin "47") (pinfunction "PGED2/SOSCI/T4CK/CN1/RC13_47") (pintype "passive"))
    )
    (net (code "89") (name "unconnected-(D1-PGED3{slash}AN0{slash}CN2{slash}RB0-Pad16)") (class "Default")
      (node (ref "D1") (pin "16") (pinfunction "PGED3/AN0/CN2/RB0_16") (pintype "passive"))
    )
    (net (code "90") (name "unconnected-(D1-PWM1H{slash}RE1-Pad61)") (class "Default")
      (node (ref "D1") (pin "61") (pinfunction "PWM1H/RE1_61") (pintype "passive"))
    )
    (net (code "91") (name "unconnected-(D1-PWM1L{slash}FLT8{slash}RE0-Pad60)") (class "Default")
      (node (ref "D1") (pin "60") (pinfunction "PWM1L/FLT8/RE0_60") (pintype "passive"))
    )
    (net (code "92") (name "unconnected-(D1-PWM2H{slash}RE3-Pad63)") (class "Default")
      (node (ref "D1") (pin "63") (pinfunction "PWM2H/RE3_63") (pintype "passive"))
    )
    (net (code "93") (name "unconnected-(D1-PWM2L{slash}RE2-Pad62)") (class "Default")
      (node (ref "D1") (pin "62") (pinfunction "PWM2L/RE2_62") (pintype "passive"))
    )
    (net (code "94") (name "unconnected-(D1-PWM3H{slash}RE5-Pad1)") (class "Default")
      (node (ref "D1") (pin "1") (pinfunction "PWM3H/RE5_1") (pintype "passive"))
    )
    (net (code "95") (name "unconnected-(D1-PWM3L{slash}RE4-Pad64)") (class "Default")
      (node (ref "D1") (pin "64") (pinfunction "PWM3L/RE4_64") (pintype "passive"))
    )
    (net (code "96") (name "unconnected-(D1-PWM4H{slash}RE7-Pad3)") (class "Default")
      (node (ref "D1") (pin "3") (pinfunction "PWM4H/RE7_3") (pintype "passive"))
    )
    (net (code "97") (name "unconnected-(D1-PWM4L{slash}RE6-Pad2)") (class "Default")
      (node (ref "D1") (pin "2") (pinfunction "PWM4L/RE6_2") (pintype "passive"))
    )
    (net (code "98") (name "unconnected-(D1-PWM6H{slash}CN14{slash}RD5-Pad53)") (class "Default")
      (node (ref "D1") (pin "53") (pinfunction "PWM6H/CN14/RD5_53") (pintype "passive"))
    )
    (net (code "99") (name "unconnected-(D1-PWM6L{slash}CN13{slash}RD4-Pad52)") (class "Default")
      (node (ref "D1") (pin "52") (pinfunction "PWM6L/CN13/RD4_52") (pintype "passive"))
    )
    (net (code "100") (name "unconnected-(D1-SCK2{slash}FLT12{slash}CN8{slash}RG6-Pad4)") (class "Default")
      (node (ref "D1") (pin "4") (pinfunction "SCK2/FLT12/CN8/RG6_4") (pintype "passive"))
    )
    (net (code "101") (name "unconnected-(D1-SCL1{slash}RG2-Pad37)") (class "Default")
      (node (ref "D1") (pin "37") (pinfunction "SCL1/RG2_37") (pintype "passive"))
    )
    (net (code "102") (name "unconnected-(D1-SDA1{slash}RG3-Pad36)") (class "Default")
      (node (ref "D1") (pin "36") (pinfunction "SDA1/RG3_36") (pintype "passive"))
    )
    (net (code "103") (name "unconnected-(D1-SDI2{slash}FLT11{slash}CN9{slash}RG7-Pad5)") (class "Default")
      (node (ref "D1") (pin "5") (pinfunction "SDI2/FLT11/CN9/RG7_5") (pintype "passive"))
    )
    (net (code "104") (name "unconnected-(D1-SDO2{slash}FLT10{slash}CN10{slash}RG8-Pad6)") (class "Default")
      (node (ref "D1") (pin "6") (pinfunction "SDO2/FLT10/CN10/RG8_6") (pintype "passive"))
    )
    (net (code "105") (name "unconnected-(D1-TCK{slash}AN12{slash}RB12-Pad27)") (class "Default")
      (node (ref "D1") (pin "27") (pinfunction "TCK/AN12/RB12_27") (pintype "passive"))
    )
    (net (code "106") (name "unconnected-(D1-TDI{slash}AN13{slash}RB13-Pad28)") (class "Default")
      (node (ref "D1") (pin "28") (pinfunction "TDI/AN13/RB13_28") (pintype "passive"))
    )
    (net (code "107") (name "unconnected-(D1-TDO{slash}AN11{slash}RB11-Pad24)") (class "Default")
      (node (ref "D1") (pin "24") (pinfunction "TDO/AN11/RB11_24") (pintype "passive"))
    )
    (net (code "108") (name "unconnected-(D1-TMS{slash}AN10{slash}RB10-Pad23)") (class "Default")
      (node (ref "D1") (pin "23") (pinfunction "TMS/AN10/RB10_23") (pintype "passive"))
    )
    (net (code "109") (name "unconnected-(D1-U1RX{slash}SDI1{slash}RF2-Pad34)") (class "Default")
      (node (ref "D1") (pin "34") (pinfunction "U1RX/SDI1/RF2_34") (pintype "passive"))
    )
    (net (code "110") (name "unconnected-(D1-U1TX{slash}SDO1{slash}RF3-Pad33)") (class "Default")
      (node (ref "D1") (pin "33") (pinfunction "U1TX/SDO1/RF3_33") (pintype "passive"))
    )
    (net (code "111") (name "unconnected-(D1-_SS2{slash}FLT9{slash}SYNCI2{slash}CN11{slash}RG9-Pad8)") (class "Default")
      (node (ref "D1") (pin "8") (pinfunction "_SS2/FLT9/SYNCI2/CN11/RG9_8") (pintype "passive"))
    )
    (net (code "112") (name "unconnected-(H1-{slash}RD-Pad3)") (class "Default")
      (node (ref "H1") (pin "3") (pinfunction "/RD_3") (pintype "passive"))
    )
    (net (code "113") (name "unconnected-(X3-Pad6)") (class "Default")
      (node (ref "X3") (pin "6") (pinfunction "6_6") (pintype "passive"))
    )
    (net (code "114") (name "{slash}MCLR") (class "Default")
      (node (ref "R11") (pin "1") (pinfunction "1_1") (pintype "passive"))
      (node (ref "R32") (pin "2") (pinfunction "2_2") (pintype "passive"))
      (node (ref "X3") (pin "1") (pinfunction "1_1") (pintype "passive"))
    )
  )
)
